# schematic.net
KiCad netlist of a schematic drawn in EAGLE
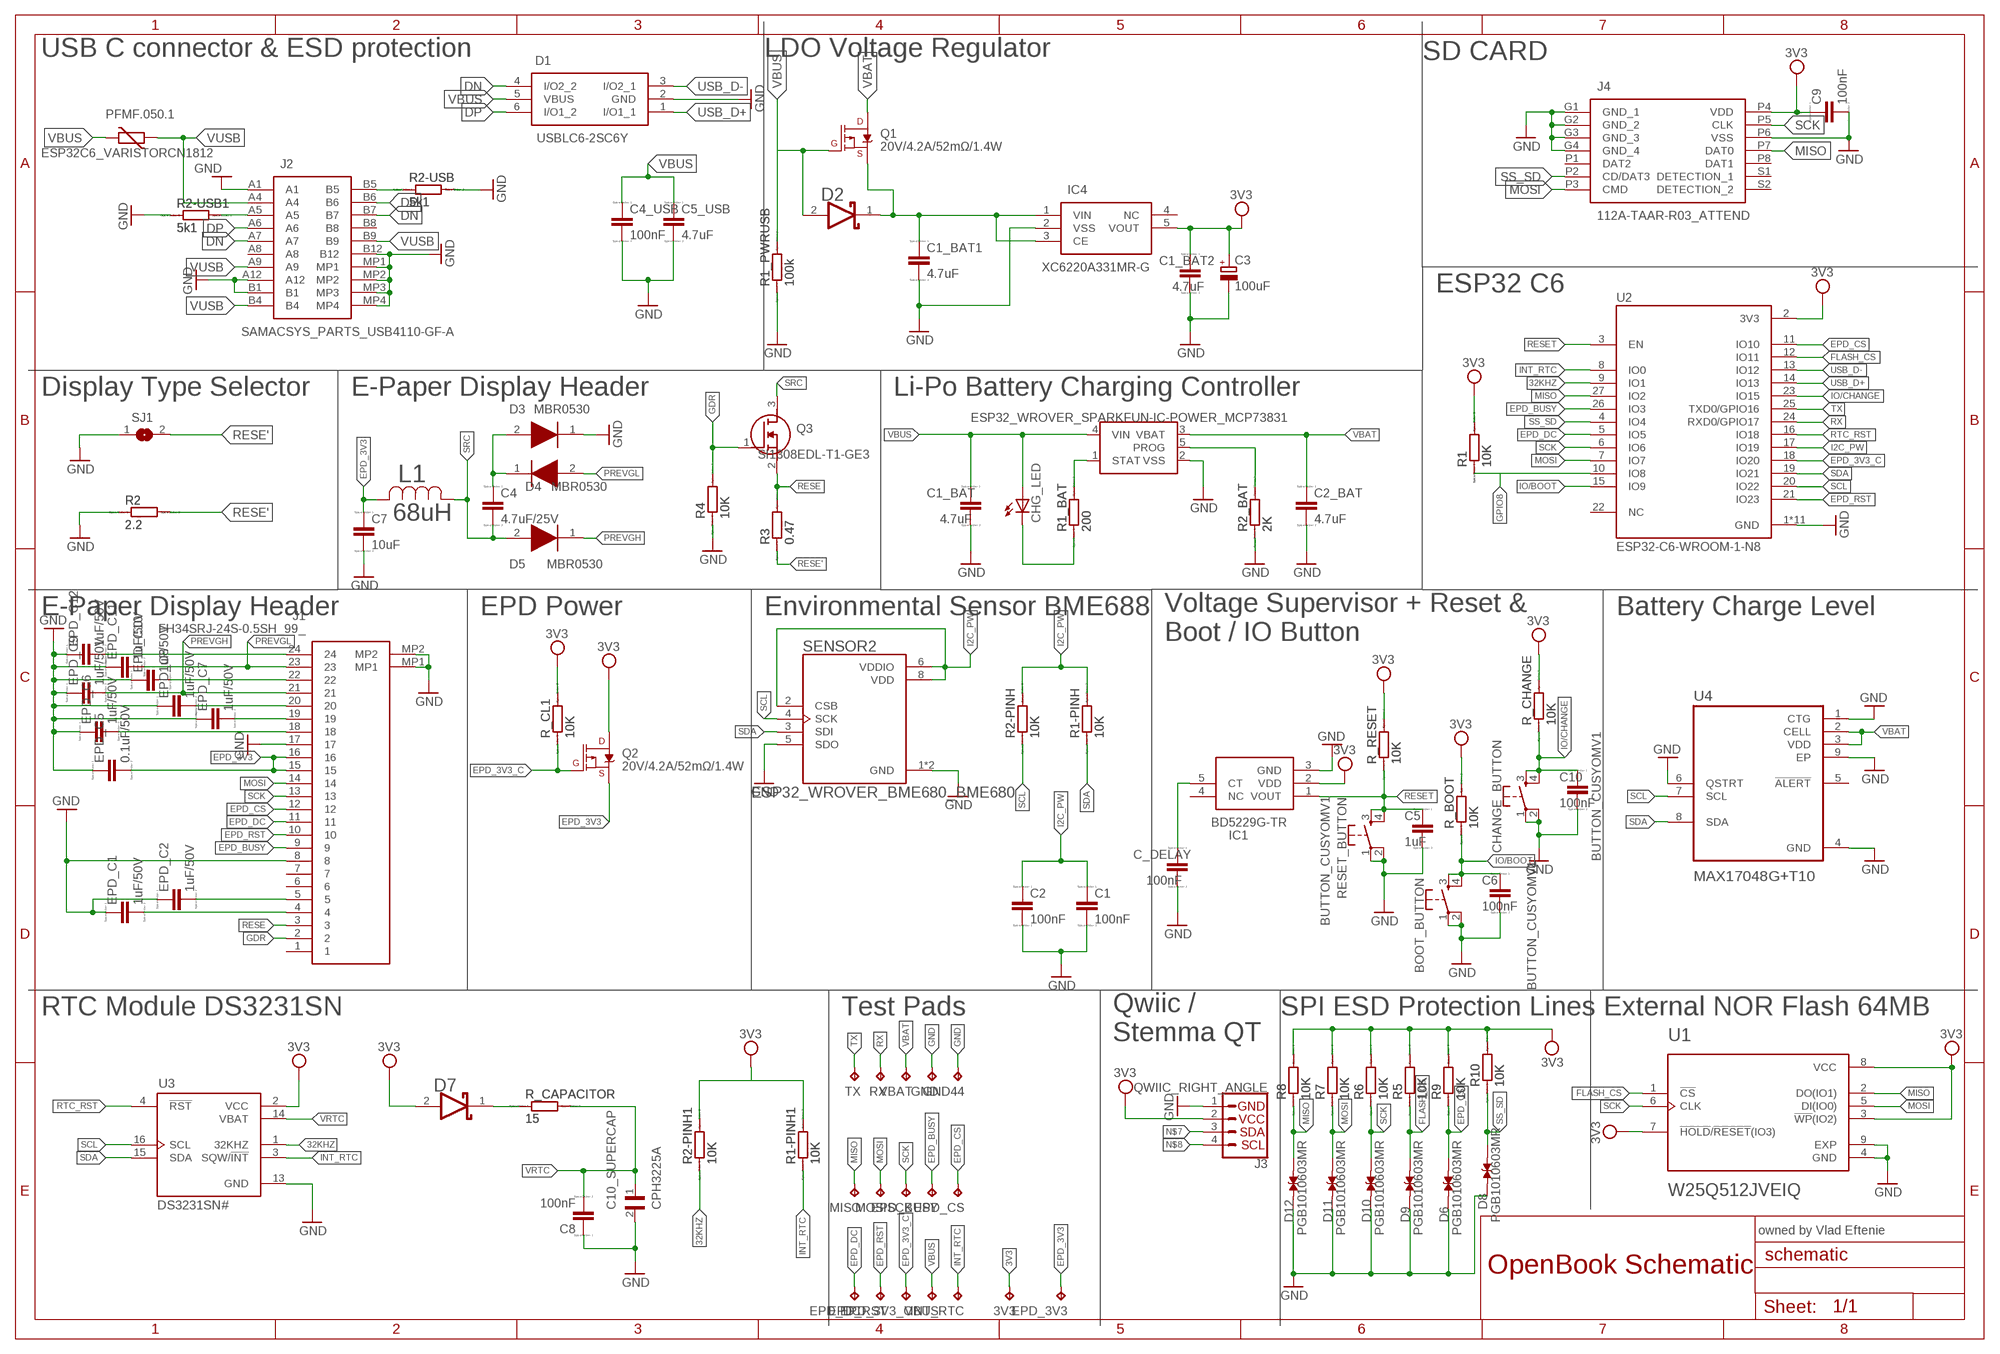
[diagram p0: schematic, sheet 1]

(export (version "E")
  (design (tool "Eeschema 10.0.6"))
  (components
    (comp (ref "3V3")
      (value "TPTP20R")
      (footprint "eagle-import:TP20R")
      (libsource (lib "eagle-import") (part "TPTP20R"))
    )
    (comp (ref "BOOT_BUTTON")
      (value "BUTTON_CUSYOMV1")
      (footprint "eagle-import:MYBUTTON")
      (libsource (lib "eagle-import") (part "BUTTON_CUSYOMV1"))
    )
    (comp (ref "C1")
      (value "100nF")
      (footprint "eagle-import:ESP32_WROVER_EAGLE-LTSPICE_C0402")
      (libsource (lib "eagle-import") (part "ESP32_WROVER_EAGLE-LTSPICE_CC0402"))
    )
    (comp (ref "C1_BAT")
      (value "4.7uF")
      (footprint "eagle-import:ESP32_WROVER_EAGLE-LTSPICE_C0402")
      (libsource (lib "eagle-import") (part "ESP32_WROVER_EAGLE-LTSPICE_CC0402"))
    )
    (comp (ref "C1_BAT1")
      (value "4.7uF")
      (footprint "eagle-import:ESP32_WROVER_EAGLE-LTSPICE_C0402")
      (libsource (lib "eagle-import") (part "ESP32_WROVER_EAGLE-LTSPICE_CC0402"))
    )
    (comp (ref "C1_BAT2")
      (value "4.7uF")
      (footprint "eagle-import:ESP32_WROVER_EAGLE-LTSPICE_C0402")
      (libsource (lib "eagle-import") (part "ESP32_WROVER_EAGLE-LTSPICE_CC0402"))
    )
    (comp (ref "C2")
      (value "100nF")
      (footprint "eagle-import:ESP32_WROVER_EAGLE-LTSPICE_C0402")
      (libsource (lib "eagle-import") (part "ESP32_WROVER_EAGLE-LTSPICE_CC0402"))
    )
    (comp (ref "C2_BAT")
      (value "4.7uF")
      (footprint "eagle-import:ESP32_WROVER_EAGLE-LTSPICE_C0402")
      (libsource (lib "eagle-import") (part "ESP32_WROVER_EAGLE-LTSPICE_CC0402"))
    )
    (comp (ref "C3")
      (value "100uF")
      (footprint "eagle-import:RCL_CT3528")
      (libsource (lib "eagle-import") (part "RCL_CPOL-EUCT3528"))
    )
    (comp (ref "C4")
      (value "4.7uF/25V")
      (footprint "eagle-import:ESP32_WROVER_EAGLE-LTSPICE_C0402")
      (libsource (lib "eagle-import") (part "ESP32_WROVER_EAGLE-LTSPICE_CC0402"))
    )
    (comp (ref "C4_USB")
      (value "100nF")
      (footprint "eagle-import:ESP32_WROVER_EAGLE-LTSPICE_C0402")
      (libsource (lib "eagle-import") (part "ESP32_WROVER_EAGLE-LTSPICE_CC0402"))
    )
    (comp (ref "C5")
      (value "1uF")
      (footprint "eagle-import:ESP32_WROVER_EAGLE-LTSPICE_C0402")
      (libsource (lib "eagle-import") (part "ESP32_WROVER_EAGLE-LTSPICE_CC0402"))
    )
    (comp (ref "C5_USB")
      (value "4.7uF")
      (footprint "eagle-import:ESP32_WROVER_EAGLE-LTSPICE_C0402")
      (libsource (lib "eagle-import") (part "ESP32_WROVER_EAGLE-LTSPICE_CC0402"))
    )
    (comp (ref "C6")
      (value "100nF")
      (footprint "eagle-import:ESP32_WROVER_EAGLE-LTSPICE_C0402")
      (libsource (lib "eagle-import") (part "ESP32_WROVER_EAGLE-LTSPICE_CC0402"))
    )
    (comp (ref "C7")
      (value "10uF")
      (footprint "eagle-import:ESP32_WROVER_EAGLE-LTSPICE_C0402")
      (libsource (lib "eagle-import") (part "ESP32_WROVER_EAGLE-LTSPICE_CC0402"))
    )
    (comp (ref "C8")
      (value "100nF")
      (footprint "eagle-import:ESP32_WROVER_EAGLE-LTSPICE_C0402")
      (libsource (lib "eagle-import") (part "ESP32_WROVER_EAGLE-LTSPICE_CC0402"))
    )
    (comp (ref "C9")
      (value "100nF")
      (footprint "eagle-import:ESP32_WROVER_EAGLE-LTSPICE_C0402")
      (libsource (lib "eagle-import") (part "ESP32_WROVER_EAGLE-LTSPICE_CC0402"))
    )
    (comp (ref "C10")
      (value "100nF")
      (footprint "eagle-import:ESP32_WROVER_EAGLE-LTSPICE_C0402")
      (libsource (lib "eagle-import") (part "ESP32_WROVER_EAGLE-LTSPICE_CC0402"))
    )
    (comp (ref "C10_SUPERCAP")
      (value "CPH3225A")
      (footprint "eagle-import:CAPCP3225X100N")
      (fields (field (name "MF") "Seiko Instruments"))
      (libsource (lib "eagle-import") (part "CPH3225A"))
    )
    (comp (ref "CHANGE_BUTTON")
      (value "BUTTON_CUSYOMV1")
      (footprint "eagle-import:MYBUTTON")
      (libsource (lib "eagle-import") (part "BUTTON_CUSYOMV1"))
    )
    (comp (ref "CHG_LED")
      (value "ADAFRUIT_LEDCHIP-LED0603")
      (footprint "eagle-import:ADAFRUIT_CHIP-LED0603")
      (libsource (lib "eagle-import") (part "ADAFRUIT_LEDCHIP-LED0603"))
    )
    (comp (ref "C_DELAY")
      (value "100nF")
      (footprint "eagle-import:ESP32_WROVER_EAGLE-LTSPICE_C0402")
      (libsource (lib "eagle-import") (part "ESP32_WROVER_EAGLE-LTSPICE_CC0402"))
    )
    (comp (ref "D1")
      (value "USBLC6-2SC6Y")
      (footprint "eagle-import:SOT95P280X145-6N")
      (fields (field (name "MF") "STMicroelectronics"))
      (libsource (lib "eagle-import") (part "USBLC6-2SC6Y"))
    )
    (comp (ref "D2")
      (value "ESP32_WROVER_AVX---SD0805S020S1R0_AVX_SD0805S020S1R0_0_0AVX_SD0805S020S1R0_0_0")
      (footprint "eagle-import:ESP32_WROVER_AVX---SD0805S020S1R0_AVX_SD0805S020S1R0_0")
      (fields
        (field (name "DIGIKEY_PART_NUMBER") "478-7800-1-ND")
        (field (name "MF") "AVX")
        (field (name "MOUSER_PART_NUMBER") "581-SD0805S020S1R0")
      )
      (libsource (lib "eagle-import") (part "ESP32_WROVER_AVX---SD0805S020S1R0_AVX_SD0805S020S1R0_0_0AVX_SD0805S020S1R0_0_0"))
    )
    (comp (ref "D3")
      (value "MBR0530")
      (footprint "eagle-import:SOD3716X135N")
      (fields (field (name "MF") "ON Semiconductor"))
      (libsource (lib "eagle-import") (part "MBR0530"))
    )
    (comp (ref "D4")
      (value "MBR0530")
      (footprint "eagle-import:SOD3716X135N")
      (fields (field (name "MF") "ON Semiconductor"))
      (libsource (lib "eagle-import") (part "MBR0530"))
    )
    (comp (ref "D5")
      (value "MBR0530")
      (footprint "eagle-import:SOD3716X135N")
      (fields (field (name "MF") "ON Semiconductor"))
      (libsource (lib "eagle-import") (part "MBR0530"))
    )
    (comp (ref "D6")
      (value "PGB1010603MR")
      (footprint "eagle-import:DIOC1608X36N")
      (fields (field (name "MF") "Littelfuse Inc."))
      (libsource (lib "eagle-import") (part "PGB1010603MR"))
    )
    (comp (ref "D7")
      (value "ESP32_WROVER_AVX---SD0805S020S1R0_AVX_SD0805S020S1R0_0_0AVX_SD0805S020S1R0_0_0")
      (footprint "eagle-import:ESP32_WROVER_AVX---SD0805S020S1R0_AVX_SD0805S020S1R0_0")
      (fields
        (field (name "DIGIKEY_PART_NUMBER") "478-7800-1-ND")
        (field (name "MF") "AVX")
        (field (name "MOUSER_PART_NUMBER") "581-SD0805S020S1R0")
      )
      (libsource (lib "eagle-import") (part "ESP32_WROVER_AVX---SD0805S020S1R0_AVX_SD0805S020S1R0_0_0AVX_SD0805S020S1R0_0_0"))
    )
    (comp (ref "D8")
      (value "PGB1010603MR")
      (footprint "eagle-import:DIOC1608X36N")
      (fields (field (name "MF") "Littelfuse Inc."))
      (libsource (lib "eagle-import") (part "PGB1010603MR"))
    )
    (comp (ref "D9")
      (value "PGB1010603MR")
      (footprint "eagle-import:DIOC1608X36N")
      (fields (field (name "MF") "Littelfuse Inc."))
      (libsource (lib "eagle-import") (part "PGB1010603MR"))
    )
    (comp (ref "D10")
      (value "PGB1010603MR")
      (footprint "eagle-import:DIOC1608X36N")
      (fields (field (name "MF") "Littelfuse Inc."))
      (libsource (lib "eagle-import") (part "PGB1010603MR"))
    )
    (comp (ref "D11")
      (value "PGB1010603MR")
      (footprint "eagle-import:DIOC1608X36N")
      (fields (field (name "MF") "Littelfuse Inc."))
      (libsource (lib "eagle-import") (part "PGB1010603MR"))
    )
    (comp (ref "D12")
      (value "PGB1010603MR")
      (footprint "eagle-import:DIOC1608X36N")
      (fields (field (name "MF") "Littelfuse Inc."))
      (libsource (lib "eagle-import") (part "PGB1010603MR"))
    )
    (comp (ref "EPD_3V3")
      (value "TPTP20R")
      (footprint "eagle-import:TP20R")
      (libsource (lib "eagle-import") (part "TPTP20R"))
    )
    (comp (ref "EPD_3V3_C")
      (value "TPTP20R")
      (footprint "eagle-import:TP20R")
      (libsource (lib "eagle-import") (part "TPTP20R"))
    )
    (comp (ref "EPD_BUSY")
      (value "TPTP20R")
      (footprint "eagle-import:TP20R")
      (libsource (lib "eagle-import") (part "TPTP20R"))
    )
    (comp (ref "EPD_C1")
      (value "1uF/50V")
      (footprint "eagle-import:ESP32_WROVER_EAGLE-LTSPICE_C0402")
      (libsource (lib "eagle-import") (part "ESP32_WROVER_EAGLE-LTSPICE_CC0402"))
    )
    (comp (ref "EPD_C2")
      (value "1uF/50V")
      (footprint "eagle-import:ESP32_WROVER_EAGLE-LTSPICE_C0402")
      (libsource (lib "eagle-import") (part "ESP32_WROVER_EAGLE-LTSPICE_CC0402"))
    )
    (comp (ref "EPD_C5")
      (value "0.1uF/50V")
      (footprint "eagle-import:ESP32_WROVER_EAGLE-LTSPICE_C0402")
      (libsource (lib "eagle-import") (part "ESP32_WROVER_EAGLE-LTSPICE_CC0402"))
    )
    (comp (ref "EPD_C6")
      (value "1uF/50V")
      (footprint "eagle-import:ESP32_WROVER_EAGLE-LTSPICE_C0402")
      (libsource (lib "eagle-import") (part "ESP32_WROVER_EAGLE-LTSPICE_CC0402"))
    )
    (comp (ref "EPD_C7")
      (value "1uF/50V")
      (footprint "eagle-import:ESP32_WROVER_EAGLE-LTSPICE_C0402")
      (libsource (lib "eagle-import") (part "ESP32_WROVER_EAGLE-LTSPICE_CC0402"))
    )
    (comp (ref "EPD_C8")
      (value "1uF/50V")
      (footprint "eagle-import:ESP32_WROVER_EAGLE-LTSPICE_C0402")
      (libsource (lib "eagle-import") (part "ESP32_WROVER_EAGLE-LTSPICE_CC0402"))
    )
    (comp (ref "EPD_C9")
      (value "1uF/50V")
      (footprint "eagle-import:ESP32_WROVER_EAGLE-LTSPICE_C0402")
      (libsource (lib "eagle-import") (part "ESP32_WROVER_EAGLE-LTSPICE_CC0402"))
    )
    (comp (ref "EPD_C10")
      (value "1uF/50V")
      (footprint "eagle-import:ESP32_WROVER_EAGLE-LTSPICE_C0402")
      (libsource (lib "eagle-import") (part "ESP32_WROVER_EAGLE-LTSPICE_CC0402"))
    )
    (comp (ref "EPD_C11")
      (value "1uF/50V")
      (footprint "eagle-import:ESP32_WROVER_EAGLE-LTSPICE_C0402")
      (libsource (lib "eagle-import") (part "ESP32_WROVER_EAGLE-LTSPICE_CC0402"))
    )
    (comp (ref "EPD_C12")
      (value "1uF/50V")
      (footprint "eagle-import:ESP32_WROVER_EAGLE-LTSPICE_C0402")
      (libsource (lib "eagle-import") (part "ESP32_WROVER_EAGLE-LTSPICE_CC0402"))
    )
    (comp (ref "EPD_CS")
      (value "TPTP20R")
      (footprint "eagle-import:TP20R")
      (libsource (lib "eagle-import") (part "TPTP20R"))
    )
    (comp (ref "EPD_DC")
      (value "TPTP20R")
      (footprint "eagle-import:TP20R")
      (libsource (lib "eagle-import") (part "TPTP20R"))
    )
    (comp (ref "EPD_RST")
      (value "TPTP20R")
      (footprint "eagle-import:TP20R")
      (libsource (lib "eagle-import") (part "TPTP20R"))
    )
    (comp (ref "GND")
      (value "TPTP20R")
      (footprint "eagle-import:TP20R")
      (libsource (lib "eagle-import") (part "TPTP20R"))
    )
    (comp (ref "GND44")
      (value "TPTP20R")
      (footprint "eagle-import:TP20R")
      (libsource (lib "eagle-import") (part "TPTP20R"))
    )
    (comp (ref "IC1")
      (value "BD5229G-TR")
      (footprint "eagle-import:SOT95P280X125-5N")
      (fields (field (name "MOUSER_PART_NUMBER") "755-BD5229G-TR"))
      (libsource (lib "eagle-import") (part "BD5229G-TR"))
    )
    (comp (ref "IC4")
      (value "XC6220A331MR-G")
      (footprint "eagle-import:SOT95P280X120-5N")
      (fields (field (name "MOUSER_PART_NUMBER") "865-XC6220A331MR-G"))
      (libsource (lib "eagle-import") (part "XC6220A331MR-G"))
    )
    (comp (ref "INT_RTC")
      (value "TPTP20R")
      (footprint "eagle-import:TP20R")
      (libsource (lib "eagle-import") (part "TPTP20R"))
    )
    (comp (ref "J1")
      (value "FH34SRJ-24S-0.5SH_99_")
      (footprint "eagle-import:FH34SRJ24S05SH99")
      (fields
        (field (name "MANUFACTURER_PART_NUMBER") "FH34SRJ-24S-0.5SH(99)")
        (field (name "MOUSER_PART_NUMBER") "798-FH34SRJ24S05SH99")
      )
      (libsource (lib "eagle-import") (part "FH34SRJ-24S-0.5SH_99_"))
    )
    (comp (ref "J2")
      (value "SAMACSYS_PARTS_USB4110-GF-A")
      (footprint "eagle-import:SAMACSYS_PARTS_USB4110GFA")
      (fields
        (field (name "MANUFACTURER_PART_NUMBER") "USB4110-GF-A")
        (field (name "MOUSER_PART_NUMBER") "640-USB4110-GF-A")
      )
      (libsource (lib "eagle-import") (part "SAMACSYS_PARTS_USB4110-GF-A"))
    )
    (comp (ref "J3")
      (value "QWIIC_RIGHT_ANGLE")
      (footprint "eagle-import:JST04_1MM_RA")
      (libsource (lib "eagle-import") (part "QWIIC_CONNECTORJS-1MM"))
    )
    (comp (ref "J4")
      (value "112A-TAAR-R03_ATTEND")
      (footprint "eagle-import:112ATAARR03ATTEND")
      (fields (field (name "MANUFACTURER_PART_NUMBER") "112A-TAAR-R03 ATTEND"))
      (libsource (lib "eagle-import") (part "112A-TAAR-R03_ATTEND"))
    )
    (comp (ref "L1")
      (value "68uH")
      (footprint "eagle-import:IND_4828-WE-TPC_WRE")
      (fields
        (field (name "MANUFACTURER_PART_NUMBER") "744043680")
        (field (name "COPYRIGHT") "Copyright (C) 2024 Ultra Librarian. All rights reserved.")
      )
      (libsource (lib "eagle-import") (part "744043680IND_4828-WE-TPC_WRE"))
    )
    (comp (ref "MCP73831")
      (value "ESP32_WROVER_SPARKFUN-IC-POWER_MCP73831")
      (footprint "eagle-import:ESP32_WROVER_SPARKFUN-IC-POWER_SOT23-5")
      (libsource (lib "eagle-import") (part "ESP32_WROVER_SPARKFUN-IC-POWER_MCP73831"))
    )
    (comp (ref "MISO")
      (value "TPTP20R")
      (footprint "eagle-import:TP20R")
      (libsource (lib "eagle-import") (part "TPTP20R"))
    )
    (comp (ref "MOSI")
      (value "TPTP20R")
      (footprint "eagle-import:TP20R")
      (libsource (lib "eagle-import") (part "TPTP20R"))
    )
    (comp (ref "PFMF.050.1")
      (value "ESP32C6_VARISTORCN1812")
      (footprint "eagle-import:ESP32C6_VARISTOR_CT_CN1812")
      (libsource (lib "eagle-import") (part "ESP32C6_VARISTORCN1812"))
    )
    (comp (ref "Q1")
      (value "20V/4.2A/52mΩ/1.4W")
      (footprint "eagle-import:ESP32_WROVER_SPARKFUN-DISCRETESEMI_SOT23-3")
      (libsource (lib "eagle-import") (part "ESP32_WROVER_SPARKFUN-DISCRETESEMI_MOSFET_PCH-DMG2305UX-7"))
    )
    (comp (ref "Q2")
      (value "20V/4.2A/52mΩ/1.4W")
      (footprint "eagle-import:ESP32_WROVER_SPARKFUN-DISCRETESEMI_SOT23-3")
      (libsource (lib "eagle-import") (part "ESP32_WROVER_SPARKFUN-DISCRETESEMI_MOSFET_PCH-DMG2305UX-7"))
    )
    (comp (ref "Q3")
      (value "SI1308EDL-T1-GE3")
      (footprint "eagle-import:SOT65P210X110-3N")
      (fields (field (name "MF") "Vishay Siliconix"))
      (libsource (lib "eagle-import") (part "SI1308EDL-T1-GE3"))
    )
    (comp (ref "R1")
      (value "10K")
      (footprint "eagle-import:ESP32_WROVER_EAGLE-LTSPICE_R0402")
      (libsource (lib "eagle-import") (part "ESP32_WROVER_EAGLE-LTSPICE_RR0402"))
    )
    (comp (ref "R1-PINH")
      (value "10K")
      (footprint "eagle-import:ESP32_WROVER_EAGLE-LTSPICE_R0402")
      (libsource (lib "eagle-import") (part "ESP32_WROVER_EAGLE-LTSPICE_RR0402"))
    )
    (comp (ref "R1-PINH1")
      (value "10K")
      (footprint "eagle-import:ESP32_WROVER_EAGLE-LTSPICE_R0402")
      (libsource (lib "eagle-import") (part "ESP32_WROVER_EAGLE-LTSPICE_RR0402"))
    )
    (comp (ref "R1_BAT")
      (value "200")
      (footprint "eagle-import:ESP32_WROVER_EAGLE-LTSPICE_R0402")
      (libsource (lib "eagle-import") (part "ESP32_WROVER_EAGLE-LTSPICE_RR0402"))
    )
    (comp (ref "R1_PWRUSB")
      (value "100k")
      (footprint "eagle-import:ESP32_WROVER_EAGLE-LTSPICE_R0402")
      (libsource (lib "eagle-import") (part "ESP32_WROVER_EAGLE-LTSPICE_RR0402"))
    )
    (comp (ref "R2")
      (value "2.2")
      (footprint "eagle-import:ESP32_WROVER_EAGLE-LTSPICE_R0402")
      (libsource (lib "eagle-import") (part "ESP32_WROVER_EAGLE-LTSPICE_RR0402"))
    )
    (comp (ref "R2-PINH")
      (value "10K")
      (footprint "eagle-import:ESP32_WROVER_EAGLE-LTSPICE_R0402")
      (libsource (lib "eagle-import") (part "ESP32_WROVER_EAGLE-LTSPICE_RR0402"))
    )
    (comp (ref "R2-PINH1")
      (value "10K")
      (footprint "eagle-import:ESP32_WROVER_EAGLE-LTSPICE_R0402")
      (libsource (lib "eagle-import") (part "ESP32_WROVER_EAGLE-LTSPICE_RR0402"))
    )
    (comp (ref "R2-USB")
      (value "5k1")
      (footprint "eagle-import:ESP32_WROVER_EAGLE-LTSPICE_R0402")
      (libsource (lib "eagle-import") (part "ESP32_WROVER_EAGLE-LTSPICE_RR0402"))
    )
    (comp (ref "R2-USB1")
      (value "5k1")
      (footprint "eagle-import:ESP32_WROVER_EAGLE-LTSPICE_R0402")
      (libsource (lib "eagle-import") (part "ESP32_WROVER_EAGLE-LTSPICE_RR0402"))
    )
    (comp (ref "R2_BAT")
      (value "2K")
      (footprint "eagle-import:ESP32_WROVER_EAGLE-LTSPICE_R0402")
      (libsource (lib "eagle-import") (part "ESP32_WROVER_EAGLE-LTSPICE_RR0402"))
    )
    (comp (ref "R3")
      (value "0.47")
      (footprint "eagle-import:ESP32_WROVER_EAGLE-LTSPICE_R0402")
      (libsource (lib "eagle-import") (part "ESP32_WROVER_EAGLE-LTSPICE_RR0402"))
    )
    (comp (ref "R4")
      (value "10K")
      (footprint "eagle-import:ESP32_WROVER_EAGLE-LTSPICE_R0402")
      (libsource (lib "eagle-import") (part "ESP32_WROVER_EAGLE-LTSPICE_RR0402"))
    )
    (comp (ref "R5")
      (value "10K")
      (footprint "eagle-import:ESP32_WROVER_EAGLE-LTSPICE_R0402")
      (libsource (lib "eagle-import") (part "ESP32_WROVER_EAGLE-LTSPICE_RR0402"))
    )
    (comp (ref "R6")
      (value "10K")
      (footprint "eagle-import:ESP32_WROVER_EAGLE-LTSPICE_R0402")
      (libsource (lib "eagle-import") (part "ESP32_WROVER_EAGLE-LTSPICE_RR0402"))
    )
    (comp (ref "R7")
      (value "10K")
      (footprint "eagle-import:ESP32_WROVER_EAGLE-LTSPICE_R0402")
      (libsource (lib "eagle-import") (part "ESP32_WROVER_EAGLE-LTSPICE_RR0402"))
    )
    (comp (ref "R8")
      (value "10K")
      (footprint "eagle-import:ESP32_WROVER_EAGLE-LTSPICE_R0402")
      (libsource (lib "eagle-import") (part "ESP32_WROVER_EAGLE-LTSPICE_RR0402"))
    )
    (comp (ref "R9")
      (value "10K")
      (footprint "eagle-import:ESP32_WROVER_EAGLE-LTSPICE_R0402")
      (libsource (lib "eagle-import") (part "ESP32_WROVER_EAGLE-LTSPICE_RR0402"))
    )
    (comp (ref "R10")
      (value "10K")
      (footprint "eagle-import:ESP32_WROVER_EAGLE-LTSPICE_R0402")
      (libsource (lib "eagle-import") (part "ESP32_WROVER_EAGLE-LTSPICE_RR0402"))
    )
    (comp (ref "RESET_BUTTON")
      (value "BUTTON_CUSYOMV1")
      (footprint "eagle-import:MYBUTTON")
      (libsource (lib "eagle-import") (part "BUTTON_CUSYOMV1"))
    )
    (comp (ref "RX")
      (value "TPTP20R")
      (footprint "eagle-import:TP20R")
      (libsource (lib "eagle-import") (part "TPTP20R"))
    )
    (comp (ref "R_BOOT")
      (value "10K")
      (footprint "eagle-import:ESP32_WROVER_EAGLE-LTSPICE_R0402")
      (libsource (lib "eagle-import") (part "ESP32_WROVER_EAGLE-LTSPICE_RR0402"))
    )
    (comp (ref "R_CAPACITOR")
      (value "15")
      (footprint "eagle-import:ESP32_WROVER_EAGLE-LTSPICE_R0402")
      (libsource (lib "eagle-import") (part "ESP32_WROVER_EAGLE-LTSPICE_RR0402"))
    )
    (comp (ref "R_CHANGE")
      (value "10K")
      (footprint "eagle-import:ESP32_WROVER_EAGLE-LTSPICE_R0402")
      (libsource (lib "eagle-import") (part "ESP32_WROVER_EAGLE-LTSPICE_RR0402"))
    )
    (comp (ref "R_CL1")
      (value "10K")
      (footprint "eagle-import:ESP32_WROVER_EAGLE-LTSPICE_R0402")
      (libsource (lib "eagle-import") (part "ESP32_WROVER_EAGLE-LTSPICE_RR0402"))
    )
    (comp (ref "R_RESET")
      (value "10K")
      (footprint "eagle-import:ESP32_WROVER_EAGLE-LTSPICE_R0402")
      (libsource (lib "eagle-import") (part "ESP32_WROVER_EAGLE-LTSPICE_RR0402"))
    )
    (comp (ref "SCK")
      (value "TPTP20R")
      (footprint "eagle-import:TP20R")
      (libsource (lib "eagle-import") (part "TPTP20R"))
    )
    (comp (ref "SENSOR2")
      (value "ESP32_WROVER_BME680_BME680")
      (footprint "eagle-import:ESP32_WROVER_BME680_PSON80P300X300X100-8N")
      (fields (field (name "MF") "Bosch Sensortec") (field (name "MP") "BME680"))
      (libsource (lib "eagle-import") (part "ESP32_WROVER_BME680_BME680"))
    )
    (comp (ref "SJ1") (value "SJ") (footprint "eagle-import:SJ") (libsource (lib "eagle-import") (part "SJ")))
    (comp (ref "TX")
      (value "TPTP20R")
      (footprint "eagle-import:TP20R")
      (libsource (lib "eagle-import") (part "TPTP20R"))
    )
    (comp (ref "U1")
      (value "W25Q512JVEIQ")
      (footprint "eagle-import:SON127P600X800X80-9N")
      (fields (field (name "MF") "Winbond Electronics"))
      (libsource (lib "eagle-import") (part "W25Q512JVEIQ"))
    )
    (comp (ref "U2")
      (value "ESP32-C6-WROOM-1-N8")
      (footprint "eagle-import:XCVR_ESP32-C6-WROOM-1-N8")
      (fields (field (name "MF") "Espressif Systems"))
      (libsource (lib "eagle-import") (part "ESP32-C6-WROOM-1-N8"))
    )
    (comp (ref "U3")
      (value "DS3231SN#")
      (footprint "eagle-import:SOIC127P1032X265-16N")
      (fields (field (name "MF") "Analog Devices"))
      (libsource (lib "eagle-import") (part "DS3231SN#"))
    )
    (comp (ref "U4")
      (value "MAX17048G+T10")
      (footprint "eagle-import:SON50P200X200X80-9N")
      (fields (field (name "MF") "Analog Devices"))
      (libsource (lib "eagle-import") (part "MAX17048G+T10"))
    )
    (comp (ref "VBAT")
      (value "TPTP20R")
      (footprint "eagle-import:TP20R")
      (libsource (lib "eagle-import") (part "TPTP20R"))
    )
    (comp (ref "VBUS")
      (value "TPTP20R")
      (footprint "eagle-import:TP20R")
      (libsource (lib "eagle-import") (part "TPTP20R"))
    )
  )
  (nets
    (net (code "1") (name "3V3") (class "Default")
      (node (ref "3V3") (pin "TP") (pinfunction "TP_TP") (pintype "input"))
      (node (ref "C1_BAT2") (pin "1") (pinfunction "1_1") (pintype "passive"))
      (node (ref "C3") (pin "+") (pinfunction "+_+") (pintype "passive"))
      (node (ref "C9") (pin "1") (pinfunction "1_1") (pintype "passive"))
      (node (ref "D7") (pin "2") (pinfunction "ANODE_2") (pintype "bidirectional"))
      (node (ref "IC1") (pin "2") (pinfunction "VDD_2") (pintype "bidirectional"))
      (node (ref "IC4") (pin "5") (pinfunction "VOUT_5") (pintype "bidirectional"))
      (node (ref "J3") (pin "2") (pinfunction "2_2") (pintype "power_in"))
      (node (ref "J4") (pin "P4") (pinfunction "VDD_P4") (pintype "bidirectional"))
      (node (ref "Q2") (pin "3") (pinfunction "D_3") (pintype "bidirectional"))
      (node (ref "R1") (pin "2") (pinfunction "2_2") (pintype "passive"))
      (node (ref "R10") (pin "2") (pinfunction "2_2") (pintype "passive"))
      (node (ref "R5") (pin "2") (pinfunction "2_2") (pintype "passive"))
      (node (ref "R6") (pin "2") (pinfunction "2_2") (pintype "passive"))
      (node (ref "R7") (pin "2") (pinfunction "2_2") (pintype "passive"))
      (node (ref "R8") (pin "2") (pinfunction "2_2") (pintype "passive"))
      (node (ref "R9") (pin "2") (pinfunction "2_2") (pintype "passive"))
      (node (ref "R_BOOT") (pin "2") (pinfunction "2_2") (pintype "passive"))
      (node (ref "R_CHANGE") (pin "2") (pinfunction "2_2") (pintype "passive"))
      (node (ref "R_CL1") (pin "2") (pinfunction "2_2") (pintype "passive"))
      (node (ref "R_RESET") (pin "2") (pinfunction "2_2") (pintype "passive"))
      (node (ref "U1") (pin "3") (pinfunction "~{WP}(IO2)_3") (pintype "bidirectional"))
      (node (ref "U1") (pin "7") (pinfunction "~{HOLD}/~{RESET}(IO3)_7") (pintype "bidirectional"))
      (node (ref "U1") (pin "8") (pinfunction "VCC_8") (pintype "power_in"))
      (node (ref "U2") (pin "2") (pinfunction "3V3_2") (pintype "power_in"))
      (node (ref "U3") (pin "2") (pinfunction "VCC_2") (pintype "power_in"))
    )
    (net (code "2") (name "32KHZ") (class "Default")
      (node (ref "R2-PINH1") (pin "1") (pinfunction "1_1") (pintype "passive"))
      (node (ref "U2") (pin "9") (pinfunction "IO1_9") (pintype "bidirectional"))
      (node (ref "U3") (pin "1") (pinfunction "32KHZ_1") (pintype "output"))
    )
    (net (code "3") (name "DN") (class "Default")
      (node (ref "D1") (pin "4") (pinfunction "I/O2_2_4") (pintype "bidirectional"))
      (node (ref "J2") (pin "A7") (pinfunction "A7_A7") (pintype "bidirectional"))
      (node (ref "J2") (pin "B7") (pinfunction "B7_B7") (pintype "bidirectional"))
    )
    (net (code "4") (name "DP") (class "Default")
      (node (ref "D1") (pin "6") (pinfunction "I/O1_2_6") (pintype "bidirectional"))
      (node (ref "J2") (pin "A6") (pinfunction "A6_A6") (pintype "bidirectional"))
      (node (ref "J2") (pin "B6") (pinfunction "B6_B6") (pintype "bidirectional"))
    )
    (net (code "5") (name "EPD_3V3") (class "Default")
      (node (ref "C7") (pin "1") (pinfunction "1_1") (pintype "passive"))
      (node (ref "EPD_3V3") (pin "TP") (pinfunction "TP_TP") (pintype "input"))
      (node (ref "EPD_C5") (pin "2") (pinfunction "2_2") (pintype "passive"))
      (node (ref "J1") (pin "15") (pinfunction "15_15") (pintype "bidirectional"))
      (node (ref "J1") (pin "16") (pinfunction "16_16") (pintype "bidirectional"))
      (node (ref "L1") (pin "2") (pinfunction "2_2") (pintype "passive"))
      (node (ref "Q2") (pin "2") (pinfunction "S_2") (pintype "bidirectional"))
    )
    (net (code "6") (name "EPD_3V3_C") (class "Default")
      (node (ref "EPD_3V3_C") (pin "TP") (pinfunction "TP_TP") (pintype "input"))
      (node (ref "Q2") (pin "1") (pinfunction "G_1") (pintype "bidirectional"))
      (node (ref "R_CL1") (pin "1") (pinfunction "1_1") (pintype "passive"))
      (node (ref "U2") (pin "18") (pinfunction "IO20_18") (pintype "bidirectional"))
    )
    (net (code "7") (name "EPD_BUSY") (class "Default")
      (node (ref "EPD_BUSY") (pin "TP") (pinfunction "TP_TP") (pintype "input"))
      (node (ref "J1") (pin "9") (pinfunction "9_9") (pintype "bidirectional"))
      (node (ref "U2") (pin "26") (pinfunction "IO3_26") (pintype "bidirectional"))
    )
    (net (code "8") (name "EPD_CS") (class "Default")
      (node (ref "D6") (pin "2") (pinfunction "2_2") (pintype "passive"))
      (node (ref "EPD_CS") (pin "TP") (pinfunction "TP_TP") (pintype "input"))
      (node (ref "J1") (pin "12") (pinfunction "12_12") (pintype "bidirectional"))
      (node (ref "R9") (pin "1") (pinfunction "1_1") (pintype "passive"))
      (node (ref "U2") (pin "11") (pinfunction "IO10_11") (pintype "bidirectional"))
    )
    (net (code "9") (name "EPD_DC") (class "Default")
      (node (ref "EPD_DC") (pin "TP") (pinfunction "TP_TP") (pintype "input"))
      (node (ref "J1") (pin "11") (pinfunction "11_11") (pintype "bidirectional"))
      (node (ref "U2") (pin "5") (pinfunction "IO5_5") (pintype "bidirectional"))
    )
    (net (code "10") (name "EPD_RST") (class "Default")
      (node (ref "EPD_RST") (pin "TP") (pinfunction "TP_TP") (pintype "input"))
      (node (ref "J1") (pin "10") (pinfunction "10_10") (pintype "bidirectional"))
      (node (ref "U2") (pin "21") (pinfunction "IO23_21") (pintype "bidirectional"))
    )
    (net (code "11") (name "FLASH_CS") (class "Default")
      (node (ref "D9") (pin "2") (pinfunction "2_2") (pintype "passive"))
      (node (ref "R5") (pin "1") (pinfunction "1_1") (pintype "passive"))
      (node (ref "U1") (pin "1") (pinfunction "~{CS}_1") (pintype "input"))
      (node (ref "U2") (pin "12") (pinfunction "IO11_12") (pintype "bidirectional"))
    )
    (net (code "12") (name "GDR") (class "Default")
      (node (ref "J1") (pin "2") (pinfunction "2_2") (pintype "bidirectional"))
      (node (ref "Q3") (pin "1") (pinfunction "G_1") (pintype "bidirectional"))
      (node (ref "R4") (pin "2") (pinfunction "2_2") (pintype "passive"))
    )
    (net (code "13") (name "GND") (class "Default")
      (node (ref "BOOT_BUTTON") (pin "1") (pinfunction "1_1") (pintype "passive"))
      (node (ref "BOOT_BUTTON") (pin "2") (pinfunction "2_2") (pintype "passive"))
      (node (ref "C1") (pin "2") (pinfunction "2_2") (pintype "passive"))
      (node (ref "C10") (pin "2") (pinfunction "2_2") (pintype "passive"))
      (node (ref "C10_SUPERCAP") (pin "2") (pinfunction "2_2") (pintype "passive"))
      (node (ref "C1_BAT") (pin "2") (pinfunction "2_2") (pintype "passive"))
      (node (ref "C1_BAT1") (pin "2") (pinfunction "2_2") (pintype "passive"))
      (node (ref "C1_BAT2") (pin "2") (pinfunction "2_2") (pintype "passive"))
      (node (ref "C2") (pin "2") (pinfunction "2_2") (pintype "passive"))
      (node (ref "C2_BAT") (pin "2") (pinfunction "2_2") (pintype "passive"))
      (node (ref "C3") (pin "-") (pinfunction "-_-") (pintype "passive"))
      (node (ref "C4_USB") (pin "2") (pinfunction "2_2") (pintype "passive"))
      (node (ref "C5") (pin "2") (pinfunction "2_2") (pintype "passive"))
      (node (ref "C5_USB") (pin "2") (pinfunction "2_2") (pintype "passive"))
      (node (ref "C6") (pin "2") (pinfunction "2_2") (pintype "passive"))
      (node (ref "C7") (pin "2") (pinfunction "2_2") (pintype "passive"))
      (node (ref "C8") (pin "1") (pinfunction "1_1") (pintype "passive"))
      (node (ref "C9") (pin "2") (pinfunction "2_2") (pintype "passive"))
      (node (ref "CHANGE_BUTTON") (pin "1") (pinfunction "1_1") (pintype "passive"))
      (node (ref "CHANGE_BUTTON") (pin "2") (pinfunction "2_2") (pintype "passive"))
      (node (ref "C_DELAY") (pin "2") (pinfunction "2_2") (pintype "passive"))
      (node (ref "D1") (pin "2") (pinfunction "GND_2") (pintype "bidirectional"))
      (node (ref "D10") (pin "1") (pinfunction "1_1") (pintype "passive"))
      (node (ref "D11") (pin "1") (pinfunction "1_1") (pintype "passive"))
      (node (ref "D12") (pin "1") (pinfunction "1_1") (pintype "passive"))
      (node (ref "D3") (pin "1") (pinfunction "K_1") (pintype "bidirectional"))
      (node (ref "D6") (pin "1") (pinfunction "1_1") (pintype "passive"))
      (node (ref "D8") (pin "1") (pinfunction "1_1") (pintype "passive"))
      (node (ref "D9") (pin "1") (pinfunction "1_1") (pintype "passive"))
      (node (ref "EPD_C1") (pin "1") (pinfunction "1_1") (pintype "passive"))
      (node (ref "EPD_C10") (pin "1") (pinfunction "1_1") (pintype "passive"))
      (node (ref "EPD_C11") (pin "1") (pinfunction "1_1") (pintype "passive"))
      (node (ref "EPD_C12") (pin "1") (pinfunction "1_1") (pintype "passive"))
      (node (ref "EPD_C2") (pin "1") (pinfunction "1_1") (pintype "passive"))
      (node (ref "EPD_C5") (pin "1") (pinfunction "1_1") (pintype "passive"))
      (node (ref "EPD_C6") (pin "1") (pinfunction "1_1") (pintype "passive"))
      (node (ref "EPD_C7") (pin "1") (pinfunction "1_1") (pintype "passive"))
      (node (ref "EPD_C8") (pin "1") (pinfunction "1_1") (pintype "passive"))
      (node (ref "EPD_C9") (pin "1") (pinfunction "1_1") (pintype "passive"))
      (node (ref "GND") (pin "TP") (pinfunction "TP_TP") (pintype "input"))
      (node (ref "GND44") (pin "TP") (pinfunction "TP_TP") (pintype "input"))
      (node (ref "IC1") (pin "3") (pinfunction "GND_3") (pintype "bidirectional"))
      (node (ref "IC4") (pin "2") (pinfunction "VSS_2") (pintype "bidirectional"))
      (node (ref "J1") (pin "17") (pinfunction "17_17") (pintype "bidirectional"))
      (node (ref "J1") (pin "8") (pinfunction "8_8") (pintype "bidirectional"))
      (node (ref "J1") (pin "MP1") (pinfunction "MP1_MP1") (pintype "bidirectional"))
      (node (ref "J1") (pin "MP2") (pinfunction "MP2_MP2") (pintype "bidirectional"))
      (node (ref "J2") (pin "A1") (pinfunction "A1_A1") (pintype "bidirectional"))
      (node (ref "J2") (pin "A12") (pinfunction "A12_A12") (pintype "bidirectional"))
      (node (ref "J2") (pin "B1") (pinfunction "B1_B1") (pintype "bidirectional"))
      (node (ref "J2") (pin "B12") (pinfunction "B12_B12") (pintype "bidirectional"))
      (node (ref "J2") (pin "MP1") (pinfunction "MP1_MP1") (pintype "bidirectional"))
      (node (ref "J2") (pin "MP2") (pinfunction "MP2_MP2") (pintype "bidirectional"))
      (node (ref "J2") (pin "MP3") (pinfunction "MP3_MP3") (pintype "bidirectional"))
      (node (ref "J2") (pin "MP4") (pinfunction "MP4_MP4") (pintype "bidirectional"))
      (node (ref "J3") (pin "1") (pinfunction "1_1") (pintype "power_in"))
      (node (ref "J4") (pin "G1") (pinfunction "GND_1_G1") (pintype "bidirectional"))
      (node (ref "J4") (pin "G2") (pinfunction "GND_2_G2") (pintype "bidirectional"))
      (node (ref "J4") (pin "G3") (pinfunction "GND_3_G3") (pintype "bidirectional"))
      (node (ref "J4") (pin "G4") (pinfunction "GND_4_G4") (pintype "bidirectional"))
      (node (ref "J4") (pin "P6") (pinfunction "VSS_P6") (pintype "bidirectional"))
      (node (ref "MCP73831") (pin "2") (pinfunction "VSS_2") (pintype "power_in"))
      (node (ref "R1_PWRUSB") (pin "1") (pinfunction "1_1") (pintype "passive"))
      (node (ref "R2") (pin "1") (pinfunction "1_1") (pintype "passive"))
      (node (ref "R2-USB") (pin "2") (pinfunction "2_2") (pintype "passive"))
      (node (ref "R2-USB1") (pin "1") (pinfunction "1_1") (pintype "passive"))
      (node (ref "R2_BAT") (pin "1") (pinfunction "1_1") (pintype "passive"))
      (node (ref "R4") (pin "1") (pinfunction "1_1") (pintype "passive"))
      (node (ref "RESET_BUTTON") (pin "1") (pinfunction "1_1") (pintype "passive"))
      (node (ref "RESET_BUTTON") (pin "2") (pinfunction "2_2") (pintype "passive"))
      (node (ref "SENSOR2") (pin "1") (pinfunction "GND_1") (pintype "power_in"))
      (node (ref "SENSOR2") (pin "5") (pinfunction "SDO_5") (pintype "bidirectional"))
      (node (ref "SENSOR2") (pin "7") (pinfunction "GND_7") (pintype "power_in"))
      (node (ref "SJ1") (pin "1") (pinfunction "1_1") (pintype "passive"))
      (node (ref "U1") (pin "4") (pinfunction "GND_4") (pintype "power_in"))
      (node (ref "U1") (pin "9") (pinfunction "EXP_9") (pintype "passive"))
      (node (ref "U2") (pin "1") (pinfunction "GND_1") (pintype "power_in"))
      (node (ref "U2") (pin "28") (pinfunction "GND_28") (pintype "power_in"))
      (node (ref "U2") (pin "29_1") (pinfunction "GND_29_1") (pintype "power_in"))
      (node (ref "U2") (pin "29_2") (pinfunction "GND_29_2") (pintype "power_in"))
      (node (ref "U2") (pin "29_3") (pinfunction "GND_29_3") (pintype "power_in"))
      (node (ref "U2") (pin "29_4") (pinfunction "GND_29_4") (pintype "power_in"))
      (node (ref "U2") (pin "29_5") (pinfunction "GND_29_5") (pintype "power_in"))
      (node (ref "U2") (pin "29_6") (pinfunction "GND_29_6") (pintype "power_in"))
      (node (ref "U2") (pin "29_7") (pinfunction "GND_29_7") (pintype "power_in"))
      (node (ref "U2") (pin "29_8") (pinfunction "GND_29_8") (pintype "power_in"))
      (node (ref "U2") (pin "29_9") (pinfunction "GND_29_9") (pintype "power_in"))
      (node (ref "U3") (pin "13") (pinfunction "GND_13") (pintype "power_in"))
      (node (ref "U4") (pin "1") (pinfunction "CTG_1") (pintype "power_in"))
      (node (ref "U4") (pin "4") (pinfunction "GND_4") (pintype "power_in"))
      (node (ref "U4") (pin "6") (pinfunction "QSTRT_6") (pintype "input"))
      (node (ref "U4") (pin "9") (pinfunction "EP_9") (pintype "power_in"))
    )
    (net (code "15") (name "I2C_PW") (class "Default")
      (node (ref "C1") (pin "1") (pinfunction "1_1") (pintype "passive"))
      (node (ref "C2") (pin "1") (pinfunction "1_1") (pintype "passive"))
      (node (ref "R1-PINH") (pin "2") (pinfunction "2_2") (pintype "passive"))
      (node (ref "R2-PINH") (pin "2") (pinfunction "2_2") (pintype "passive"))
      (node (ref "SENSOR2") (pin "2") (pinfunction "CSB_2") (pintype "input"))
      (node (ref "SENSOR2") (pin "6") (pinfunction "VDDIO_6") (pintype "power_in"))
      (node (ref "SENSOR2") (pin "8") (pinfunction "VDD_8") (pintype "power_in"))
      (node (ref "U2") (pin "17") (pinfunction "IO19_17") (pintype "bidirectional"))
    )
    (net (code "16") (name "INT_RTC") (class "Default")
      (node (ref "INT_RTC") (pin "TP") (pinfunction "TP_TP") (pintype "input"))
      (node (ref "R1-PINH1") (pin "1") (pinfunction "1_1") (pintype "passive"))
      (node (ref "U2") (pin "8") (pinfunction "IO0_8") (pintype "bidirectional"))
      (node (ref "U3") (pin "3") (pinfunction "SQW/~{INT}_3") (pintype "output"))
    )
    (net (code "17") (name "IO{slash}BOOT") (class "Default")
      (node (ref "BOOT_BUTTON") (pin "3") (pinfunction "3_3") (pintype "passive"))
      (node (ref "BOOT_BUTTON") (pin "4") (pinfunction "4_4") (pintype "passive"))
      (node (ref "C6") (pin "1") (pinfunction "1_1") (pintype "passive"))
      (node (ref "R_BOOT") (pin "1") (pinfunction "1_1") (pintype "passive"))
      (node (ref "U2") (pin "15") (pinfunction "IO9_15") (pintype "bidirectional"))
    )
    (net (code "18") (name "IO{slash}CHANGE") (class "Default")
      (node (ref "C10") (pin "1") (pinfunction "1_1") (pintype "passive"))
      (node (ref "CHANGE_BUTTON") (pin "3") (pinfunction "3_3") (pintype "passive"))
      (node (ref "CHANGE_BUTTON") (pin "4") (pinfunction "4_4") (pintype "passive"))
      (node (ref "R_CHANGE") (pin "1") (pinfunction "1_1") (pintype "passive"))
      (node (ref "U2") (pin "23") (pinfunction "IO15_23") (pintype "bidirectional"))
    )
    (net (code "19") (name "MISO") (class "Default")
      (node (ref "D12") (pin "2") (pinfunction "2_2") (pintype "passive"))
      (node (ref "J4") (pin "P7") (pinfunction "DAT0_P7") (pintype "bidirectional"))
      (node (ref "MISO") (pin "TP") (pinfunction "TP_TP") (pintype "input"))
      (node (ref "R8") (pin "1") (pinfunction "1_1") (pintype "passive"))
      (node (ref "U1") (pin "2") (pinfunction "DO(IO1)_2") (pintype "bidirectional"))
      (node (ref "U2") (pin "27") (pinfunction "IO2_27") (pintype "bidirectional"))
    )
    (net (code "20") (name "MOSI") (class "Default")
      (node (ref "D11") (pin "2") (pinfunction "2_2") (pintype "passive"))
      (node (ref "J1") (pin "14") (pinfunction "14_14") (pintype "bidirectional"))
      (node (ref "J4") (pin "P3") (pinfunction "CMD_P3") (pintype "bidirectional"))
      (node (ref "MOSI") (pin "TP") (pinfunction "TP_TP") (pintype "input"))
      (node (ref "R7") (pin "1") (pinfunction "1_1") (pintype "passive"))
      (node (ref "U1") (pin "5") (pinfunction "DI(IO0)_5") (pintype "bidirectional"))
      (node (ref "U2") (pin "7") (pinfunction "IO7_7") (pintype "bidirectional"))
    )
    (net (code "21") (name "N$7") (class "Default")
      (node (ref "J3") (pin "3") (pinfunction "3_3") (pintype "passive"))
    )
    (net (code "22") (name "N$8") (class "Default")
      (node (ref "J3") (pin "4") (pinfunction "4_4") (pintype "passive"))
    )
    (net (code "23") (name "Net-(CHG_LED-PadC)") (class "Default")
      (node (ref "CHG_LED") (pin "C") (pinfunction "C_C") (pintype "passive"))
      (node (ref "R1_BAT") (pin "1") (pinfunction "1_1") (pintype "passive"))
    )
    (net (code "24") (name "Net-(D2-ANODE)") (class "Default")
      (node (ref "D2") (pin "2") (pinfunction "ANODE_2") (pintype "bidirectional"))
      (node (ref "Q1") (pin "1") (pinfunction "G_1") (pintype "bidirectional"))
    )
    (net (code "25") (name "Net-(D2-CATHODE)") (class "Default")
      (node (ref "C1_BAT1") (pin "1") (pinfunction "1_1") (pintype "passive"))
      (node (ref "D2") (pin "1") (pinfunction "CATHODE_1") (pintype "bidirectional"))
      (node (ref "IC4") (pin "1") (pinfunction "VIN_1") (pintype "bidirectional"))
      (node (ref "IC4") (pin "3") (pinfunction "CE_3") (pintype "bidirectional"))
      (node (ref "Q1") (pin "2") (pinfunction "S_2") (pintype "bidirectional"))
    )
    (net (code "26") (name "Net-(D3-A)") (class "Default")
      (node (ref "C4") (pin "1") (pinfunction "1_1") (pintype "passive"))
      (node (ref "D3") (pin "2") (pinfunction "A_2") (pintype "bidirectional"))
      (node (ref "D4") (pin "1") (pinfunction "K_1") (pintype "bidirectional"))
    )
    (net (code "27") (name "Net-(D7-CATHODE)") (class "Default")
      (node (ref "D7") (pin "1") (pinfunction "CATHODE_1") (pintype "bidirectional"))
      (node (ref "R_CAPACITOR") (pin "1") (pinfunction "1_1") (pintype "passive"))
    )
    (net (code "28") (name "Net-(EPD_C1-Pad2)") (class "Default")
      (node (ref "EPD_C1") (pin "2") (pinfunction "2_2") (pintype "passive"))
      (node (ref "J1") (pin "4") (pinfunction "4_4") (pintype "bidirectional"))
    )
    (net (code "29") (name "Net-(EPD_C2-Pad2)") (class "Default")
      (node (ref "EPD_C2") (pin "2") (pinfunction "2_2") (pintype "passive"))
      (node (ref "J1") (pin "5") (pinfunction "5_5") (pintype "bidirectional"))
    )
    (net (code "30") (name "Net-(EPD_C6-Pad2)") (class "Default")
      (node (ref "EPD_C6") (pin "2") (pinfunction "2_2") (pintype "passive"))
      (node (ref "J1") (pin "18") (pinfunction "18_18") (pintype "bidirectional"))
    )
    (net (code "31") (name "Net-(EPD_C7-Pad2)") (class "Default")
      (node (ref "EPD_C7") (pin "2") (pinfunction "2_2") (pintype "passive"))
      (node (ref "J1") (pin "19") (pinfunction "19_19") (pintype "bidirectional"))
    )
    (net (code "32") (name "Net-(EPD_C8-Pad2)") (class "Default")
      (node (ref "EPD_C8") (pin "2") (pinfunction "2_2") (pintype "passive"))
      (node (ref "J1") (pin "20") (pinfunction "20_20") (pintype "bidirectional"))
    )
    (net (code "33") (name "Net-(EPD_C10-Pad2)") (class "Default")
      (node (ref "EPD_C10") (pin "2") (pinfunction "2_2") (pintype "passive"))
      (node (ref "J1") (pin "22") (pinfunction "22_22") (pintype "bidirectional"))
    )
    (net (code "34") (name "Net-(EPD_C12-Pad2)") (class "Default")
      (node (ref "EPD_C12") (pin "2") (pinfunction "2_2") (pintype "passive"))
      (node (ref "J1") (pin "24") (pinfunction "24_24") (pintype "bidirectional"))
    )
    (net (code "35") (name "Net-(IC1-CT)") (class "Default")
      (node (ref "C_DELAY") (pin "1") (pinfunction "1_1") (pintype "passive"))
      (node (ref "IC1") (pin "5") (pinfunction "CT_5") (pintype "bidirectional"))
    )
    (net (code "36") (name "Net-(J2-PadA5)") (class "Default")
      (node (ref "J2") (pin "A5") (pinfunction "A5_A5") (pintype "bidirectional"))
      (node (ref "R2-USB1") (pin "2") (pinfunction "2_2") (pintype "passive"))
    )
    (net (code "37") (name "Net-(J2-PadB5)") (class "Default")
      (node (ref "J2") (pin "B5") (pinfunction "B5_B5") (pintype "bidirectional"))
      (node (ref "R2-USB") (pin "1") (pinfunction "1_1") (pintype "passive"))
    )
    (net (code "38") (name "Net-(MCP73831-PROG)") (class "Default")
      (node (ref "MCP73831") (pin "5") (pinfunction "PROG_5") (pintype "input"))
      (node (ref "R2_BAT") (pin "2") (pinfunction "2_2") (pintype "passive"))
    )
    (net (code "39") (name "Net-(MCP73831-STAT)") (class "Default")
      (node (ref "MCP73831") (pin "1") (pinfunction "STAT_1") (pintype "output"))
      (node (ref "R1_BAT") (pin "2") (pinfunction "2_2") (pintype "passive"))
    )
    (net (code "40") (name "Net-(R1-PINH1-Pad2)") (class "Default")
      (node (ref "R1-PINH1") (pin "2") (pinfunction "2_2") (pintype "passive"))
      (node (ref "R2-PINH1") (pin "2") (pinfunction "2_2") (pintype "passive"))
    )
    (net (code "41") (name "Net-(U2-IO8)") (class "Default")
      (node (ref "R1") (pin "1") (pinfunction "1_1") (pintype "passive"))
      (node (ref "U2") (pin "10") (pinfunction "IO8_10") (pintype "bidirectional"))
    )
    (net (code "42") (name "PREVGH") (class "Default")
      (node (ref "D5") (pin "1") (pinfunction "K_1") (pintype "bidirectional"))
      (node (ref "EPD_C9") (pin "2") (pinfunction "2_2") (pintype "passive"))
      (node (ref "J1") (pin "21") (pinfunction "21_21") (pintype "bidirectional"))
    )
    (net (code "43") (name "PREVGL") (class "Default")
      (node (ref "D4") (pin "2") (pinfunction "A_2") (pintype "bidirectional"))
      (node (ref "EPD_C11") (pin "2") (pinfunction "2_2") (pintype "passive"))
      (node (ref "J1") (pin "23") (pinfunction "23_23") (pintype "bidirectional"))
    )
    (net (code "44") (name "RESE") (class "Default")
      (node (ref "J1") (pin "3") (pinfunction "3_3") (pintype "bidirectional"))
      (node (ref "Q3") (pin "2") (pinfunction "S_2") (pintype "bidirectional"))
      (node (ref "R3") (pin "2") (pinfunction "2_2") (pintype "passive"))
    )
    (net (code "45") (name "RESE'") (class "Default")
      (node (ref "R2") (pin "2") (pinfunction "2_2") (pintype "passive"))
      (node (ref "R3") (pin "1") (pinfunction "1_1") (pintype "passive"))
      (node (ref "SJ1") (pin "2") (pinfunction "2_2") (pintype "passive"))
    )
    (net (code "46") (name "RESET") (class "Default")
      (node (ref "C5") (pin "1") (pinfunction "1_1") (pintype "passive"))
      (node (ref "IC1") (pin "1") (pinfunction "VOUT_1") (pintype "bidirectional"))
      (node (ref "RESET_BUTTON") (pin "3") (pinfunction "3_3") (pintype "passive"))
      (node (ref "RESET_BUTTON") (pin "4") (pinfunction "4_4") (pintype "passive"))
      (node (ref "R_RESET") (pin "1") (pinfunction "1_1") (pintype "passive"))
      (node (ref "U2") (pin "3") (pinfunction "EN_3") (pintype "input"))
    )
    (net (code "47") (name "RTC_RST") (class "Default")
      (node (ref "U2") (pin "16") (pinfunction "IO18_16") (pintype "bidirectional"))
      (node (ref "U3") (pin "4") (pinfunction "~{RST}_4") (pintype "input"))
    )
    (net (code "48") (name "RX") (class "Default")
      (node (ref "RX") (pin "TP") (pinfunction "TP_TP") (pintype "input"))
      (node (ref "U2") (pin "24") (pinfunction "RXD0/GPIO17_24") (pintype "bidirectional"))
    )
    (net (code "49") (name "SCK") (class "Default")
      (node (ref "D10") (pin "2") (pinfunction "2_2") (pintype "passive"))
      (node (ref "J1") (pin "13") (pinfunction "13_13") (pintype "bidirectional"))
      (node (ref "J4") (pin "P5") (pinfunction "CLK_P5") (pintype "bidirectional"))
      (node (ref "R6") (pin "1") (pinfunction "1_1") (pintype "passive"))
      (node (ref "SCK") (pin "TP") (pinfunction "TP_TP") (pintype "input"))
      (node (ref "U1") (pin "6") (pinfunction "CLK_6") (pintype "input"))
      (node (ref "U2") (pin "6") (pinfunction "IO6_6") (pintype "bidirectional"))
    )
    (net (code "50") (name "SCL") (class "Default")
      (node (ref "R2-PINH") (pin "1") (pinfunction "1_1") (pintype "passive"))
      (node (ref "SENSOR2") (pin "4") (pinfunction "SCK_4") (pintype "input"))
      (node (ref "U2") (pin "20") (pinfunction "IO22_20") (pintype "bidirectional"))
      (node (ref "U3") (pin "16") (pinfunction "SCL_16") (pintype "input"))
      (node (ref "U4") (pin "7") (pinfunction "SCL_7") (pintype "input"))
    )
    (net (code "51") (name "SDA") (class "Default")
      (node (ref "R1-PINH") (pin "1") (pinfunction "1_1") (pintype "passive"))
      (node (ref "SENSOR2") (pin "3") (pinfunction "SDI_3") (pintype "bidirectional"))
      (node (ref "U2") (pin "19") (pinfunction "IO21_19") (pintype "bidirectional"))
      (node (ref "U3") (pin "15") (pinfunction "SDA_15") (pintype "bidirectional"))
      (node (ref "U4") (pin "8") (pinfunction "SDA_8") (pintype "bidirectional"))
    )
    (net (code "52") (name "SRC") (class "Default")
      (node (ref "C4") (pin "2") (pinfunction "2_2") (pintype "passive"))
      (node (ref "D5") (pin "2") (pinfunction "A_2") (pintype "bidirectional"))
      (node (ref "L1") (pin "1") (pinfunction "1_1") (pintype "passive"))
      (node (ref "Q3") (pin "3") (pinfunction "D_3") (pintype "bidirectional"))
    )
    (net (code "53") (name "SS_SD") (class "Default")
      (node (ref "D8") (pin "2") (pinfunction "2_2") (pintype "passive"))
      (node (ref "J4") (pin "P2") (pinfunction "CD/DAT3_P2") (pintype "bidirectional"))
      (node (ref "R10") (pin "1") (pinfunction "1_1") (pintype "passive"))
      (node (ref "U2") (pin "4") (pinfunction "IO4_4") (pintype "bidirectional"))
    )
    (net (code "54") (name "TX") (class "Default")
      (node (ref "TX") (pin "TP") (pinfunction "TP_TP") (pintype "input"))
      (node (ref "U2") (pin "25") (pinfunction "TXD0/GPIO16_25") (pintype "bidirectional"))
    )
    (net (code "55") (name "USB_D+") (class "Default")
      (node (ref "D1") (pin "1") (pinfunction "I/O1_1_1") (pintype "bidirectional"))
      (node (ref "U2") (pin "14") (pinfunction "IO13_14") (pintype "bidirectional"))
    )
    (net (code "56") (name "USB_D-") (class "Default")
      (node (ref "D1") (pin "3") (pinfunction "I/O2_1_3") (pintype "bidirectional"))
      (node (ref "U2") (pin "13") (pinfunction "IO12_13") (pintype "bidirectional"))
    )
    (net (code "57") (name "VBAT") (class "Default")
      (node (ref "C2_BAT") (pin "1") (pinfunction "1_1") (pintype "passive"))
      (node (ref "MCP73831") (pin "3") (pinfunction "VBAT_3") (pintype "power_in"))
      (node (ref "Q1") (pin "3") (pinfunction "D_3") (pintype "bidirectional"))
      (node (ref "U4") (pin "2") (pinfunction "CELL_2") (pintype "power_in"))
      (node (ref "U4") (pin "3") (pinfunction "VDD_3") (pintype "power_in"))
      (node (ref "VBAT") (pin "TP") (pinfunction "TP_TP") (pintype "input"))
    )
    (net (code "58") (name "VBUS") (class "Default")
      (node (ref "C1_BAT") (pin "1") (pinfunction "1_1") (pintype "passive"))
      (node (ref "C4_USB") (pin "1") (pinfunction "1_1") (pintype "passive"))
      (node (ref "C5_USB") (pin "1") (pinfunction "1_1") (pintype "passive"))
      (node (ref "CHG_LED") (pin "A") (pinfunction "A_A") (pintype "passive"))
      (node (ref "D1") (pin "5") (pinfunction "VBUS_5") (pintype "bidirectional"))
      (node (ref "MCP73831") (pin "4") (pinfunction "VIN_4") (pintype "power_in"))
      (node (ref "PFMF.050.1") (pin "2") (pinfunction "2_2") (pintype "passive"))
      (node (ref "R1_PWRUSB") (pin "2") (pinfunction "2_2") (pintype "passive"))
      (node (ref "VBUS") (pin "TP") (pinfunction "TP_TP") (pintype "input"))
    )
    (net (code "59") (name "VRTC") (class "Default")
      (node (ref "C10_SUPERCAP") (pin "1") (pinfunction "1_1") (pintype "passive"))
      (node (ref "C8") (pin "2") (pinfunction "2_2") (pintype "passive"))
      (node (ref "R_CAPACITOR") (pin "2") (pinfunction "2_2") (pintype "passive"))
      (node (ref "U3") (pin "14") (pinfunction "VBAT_14") (pintype "power_in"))
    )
    (net (code "60") (name "VUSB") (class "Default")
      (node (ref "J2") (pin "A4") (pinfunction "A4_A4") (pintype "bidirectional"))
      (node (ref "J2") (pin "A9") (pinfunction "A9_A9") (pintype "bidirectional"))
      (node (ref "J2") (pin "B4") (pinfunction "B4_B4") (pintype "bidirectional"))
      (node (ref "J2") (pin "B9") (pinfunction "B9_B9") (pintype "bidirectional"))
      (node (ref "PFMF.050.1") (pin "1") (pinfunction "1_1") (pintype "passive"))
    )
    (net (code "61") (name "unconnected-(IC1-NC-Pad4)") (class "Default")
      (node (ref "IC1") (pin "4") (pinfunction "NC_4") (pintype "no_connect"))
    )
    (net (code "62") (name "unconnected-(IC4-NC-Pad4)") (class "Default")
      (node (ref "IC4") (pin "4") (pinfunction "NC_4") (pintype "no_connect"))
    )
    (net (code "63") (name "unconnected-(J1-Pad1)") (class "Default")
      (node (ref "J1") (pin "1") (pinfunction "1_1") (pintype "bidirectional"))
    )
    (net (code "64") (name "unconnected-(J1-Pad6)") (class "Default")
      (node (ref "J1") (pin "6") (pinfunction "6_6") (pintype "bidirectional"))
    )
    (net (code "65") (name "unconnected-(J1-Pad7)") (class "Default")
      (node (ref "J1") (pin "7") (pinfunction "7_7") (pintype "bidirectional"))
    )
    (net (code "66") (name "unconnected-(J2-PadA8)") (class "Default")
      (node (ref "J2") (pin "A8") (pinfunction "A8_A8") (pintype "bidirectional"))
    )
    (net (code "67") (name "unconnected-(J2-PadB8)") (class "Default")
      (node (ref "J2") (pin "B8") (pinfunction "B8_B8") (pintype "bidirectional"))
    )
    (net (code "68") (name "unconnected-(J4-DAT1-PadP8)") (class "Default")
      (node (ref "J4") (pin "P8") (pinfunction "DAT1_P8") (pintype "bidirectional"))
    )
    (net (code "69") (name "unconnected-(J4-DAT2-PadP1)") (class "Default")
      (node (ref "J4") (pin "P1") (pinfunction "DAT2_P1") (pintype "bidirectional"))
    )
    (net (code "70") (name "unconnected-(J4-DETECTION_1-PadS1)") (class "Default")
      (node (ref "J4") (pin "S1") (pinfunction "DETECTION_1_S1") (pintype "bidirectional"))
    )
    (net (code "71") (name "unconnected-(J4-DETECTION_2-PadS2)") (class "Default")
      (node (ref "J4") (pin "S2") (pinfunction "DETECTION_2_S2") (pintype "bidirectional"))
    )
    (net (code "72") (name "unconnected-(U2-NC-Pad22)") (class "Default")
      (node (ref "U2") (pin "22") (pinfunction "NC_22") (pintype "no_connect"))
    )
    (net (code "73") (name "unconnected-(U4-~{ALERT}-Pad5)") (class "Default")
      (node (ref "U4") (pin "5") (pinfunction "~{ALERT}_5") (pintype "output"))
    )
  )
)
